# SL_Config_2E.net
KiCad netlist of a schematic drawn in Altium Designer
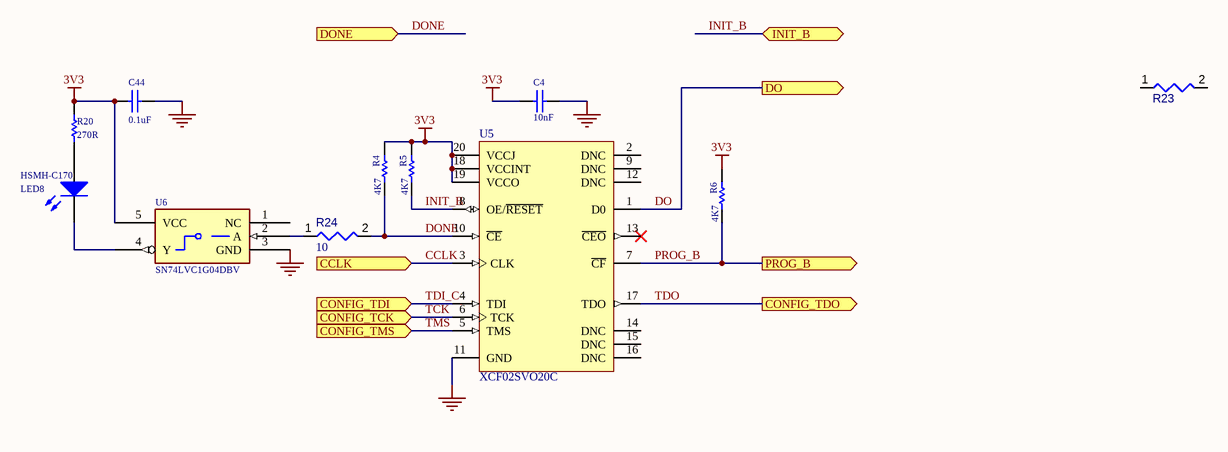
[diagram p0: SL_Config_2E.SchDoc]

(export (version "E")
  (design (tool "Eeschema 10.0.6"))
  (components
    (comp (ref "C4")
      (value "10nF")
      (footprint "CC1608-0603")
      (description "Capacitor")
      (libsource (lib "SpiritLevel_2E") (part "CAP"))
    )
    (comp (ref "C44")
      (value "0.1uF")
      (footprint "CC2012-0805")
      (description "Capacitor")
      (libsource (lib "SpiritLevel_2E") (part "CAP"))
    )
    (comp (ref "LED8")
      (value "HSMH-C170")
      (footprint "Spirit_Level_Project:SMD _LED")
      (description "Typical RED GaAs SMD LED Agilent make")
      (libsource (lib "SpiritLevel_2E") (part "HSMX-C670"))
    )
    (comp (ref "R4")
      (value "4K7")
      (footprint "Spirit_Level_Project:CR2012-0805")
      (description "Resistor")
      (libsource (lib "SpiritLevel_2E") (part "RES"))
    )
    (comp (ref "R5")
      (value "4K7")
      (footprint "Spirit_Level_Project:CR2012-0805")
      (description "Resistor")
      (libsource (lib "SpiritLevel_2E") (part "RES"))
    )
    (comp (ref "R6")
      (value "4K7")
      (footprint "Spirit_Level_Project:CR2012-0805")
      (description "Resistor")
      (libsource (lib "SpiritLevel_2E") (part "RES"))
    )
    (comp (ref "R20")
      (value "270R")
      (footprint "Spirit_Level_Project:CR2012-0805")
      (description "Resistor")
      (libsource (lib "SpiritLevel_2E") (part "RES"))
    )
    (comp (ref "R23")
      (value "Resistors")
      (description "Resistor")
      (libsource (lib "AES on LJ-AZ-064") (part "RES-2"))
    )
    (comp (ref "R24")
      (value "10")
      (footprint "RESC1005X40X25ML10T10")
      (description "Chip Resistor, 10 Ohm, +/- 5%, 0.063 W, -55 to 155 degC, 0402 (1005 Metric)")
      (fields (field (name "TOLERANCE") "5%") (field (name "POWER") "63mW"))
      (libsource (lib "AES on LJ-AZ-064") (part "RES-2"))
    )
    (comp (ref "U5")
      (value "XCF02SVO20C")
      (footprint "Spirit_Level_Project:VO20")
      (libsource (lib "SpiritLevel_2E") (part "XCF02SVO20C"))
    )
    (comp (ref "U6")
      (value "SN74LVC1G04DBV")
      (footprint "Spirit_Level_Project:SO-G5/P.95")
      (fields (field (name "MANUFACTURER") "TI"))
      (libsource (lib "SpiritLevel_2E") (part "SN74AHC1G04DBVR"))
    )
  )
  (nets
    (net (code "1") (name "/CCLK") (class "Default")
      (node (ref "U5") (pin "3") (pinfunction "CLK_3") (pintype "input"))
    )
    (net (code "2") (name "/DO") (class "Default")
      (node (ref "U5") (pin "1") (pinfunction "D0_1") (pintype "tri_state"))
    )
    (net (code "3") (name "/DONE") (class "Default")
      (node (ref "R24") (pin "2") (pinfunction "2_2") (pintype "passive"))
      (node (ref "R4") (pin "2") (pinfunction "2_2") (pintype "passive"))
      (node (ref "U5") (pin "10") (pinfunction "~{CE}_10") (pintype "input"))
    )
    (net (code "4") (name "/INIT_B") (class "Default")
      (node (ref "R5") (pin "2") (pinfunction "2_2") (pintype "passive"))
      (node (ref "U5") (pin "8") (pinfunction "OE/~{RESET}_8") (pintype "bidirectional"))
    )
    (net (code "5") (name "/PROG_B") (class "Default")
      (node (ref "R6") (pin "2") (pinfunction "2_2") (pintype "passive"))
      (node (ref "U5") (pin "7") (pinfunction "~{CF}_7") (pintype "open_collector"))
    )
    (net (code "6") (name "/TCK") (class "Default")
      (node (ref "U5") (pin "6") (pinfunction "TCK_6") (pintype "input"))
    )
    (net (code "7") (name "/TDI_C") (class "Default")
      (node (ref "U5") (pin "4") (pinfunction "TDI_4") (pintype "input"))
    )
    (net (code "8") (name "/TDO") (class "Default")
      (node (ref "U5") (pin "17") (pinfunction "TDO_17") (pintype "output"))
    )
    (net (code "9") (name "/TMS") (class "Default")
      (node (ref "U5") (pin "5") (pinfunction "TMS_5") (pintype "input"))
    )
    (net (code "10") (name "3V3") (class "Default")
      (node (ref "C4") (pin "1") (pinfunction "1_1") (pintype "passive"))
      (node (ref "C44") (pin "2") (pinfunction "2_2") (pintype "passive"))
      (node (ref "R20") (pin "2") (pinfunction "2_2") (pintype "passive"))
      (node (ref "R4") (pin "1") (pinfunction "1_1") (pintype "passive"))
      (node (ref "R5") (pin "1") (pinfunction "1_1") (pintype "passive"))
      (node (ref "R6") (pin "1") (pinfunction "1_1") (pintype "passive"))
      (node (ref "U5") (pin "18") (pinfunction "VCCINT_18") (pintype "power_in"))
      (node (ref "U5") (pin "19") (pinfunction "VCCO_19") (pintype "power_in"))
      (node (ref "U5") (pin "20") (pinfunction "VCCJ_20") (pintype "power_in"))
      (node (ref "U6") (pin "5") (pinfunction "VCC_5") (pintype "power_in"))
    )
    (net (code "11") (name "GND") (class "Default")
      (node (ref "C4") (pin "2") (pinfunction "2_2") (pintype "passive"))
      (node (ref "C44") (pin "1") (pinfunction "1_1") (pintype "passive"))
      (node (ref "U5") (pin "11") (pinfunction "GND_11") (pintype "power_in"))
      (node (ref "U6") (pin "3") (pinfunction "GND_3") (pintype "power_in"))
    )
    (net (code "12") (name "Net-(LED8-A)") (class "Default")
      (node (ref "LED8") (pin "1") (pinfunction "A_1") (pintype "passive"))
      (node (ref "R20") (pin "1") (pinfunction "1_1") (pintype "passive"))
    )
    (net (code "13") (name "Net-(LED8-K)") (class "Default")
      (node (ref "LED8") (pin "2") (pinfunction "K_2") (pintype "passive"))
      (node (ref "U6") (pin "4") (pinfunction "Y_4") (pintype "output"))
    )
    (net (code "14") (name "Net-(U6-A)") (class "Default")
      (node (ref "R24") (pin "1") (pinfunction "1_1") (pintype "passive"))
      (node (ref "U6") (pin "2") (pinfunction "A_2") (pintype "input"))
    )
    (net (code "15") (name "unconnected-(R23-Pad1)") (class "Default")
      (node (ref "R23") (pin "1") (pinfunction "1_1") (pintype "passive"))
    )
    (net (code "16") (name "unconnected-(R23-Pad2)") (class "Default")
      (node (ref "R23") (pin "2") (pinfunction "2_2") (pintype "passive"))
    )
    (net (code "17") (name "unconnected-(U5-DNC-Pad2)") (class "Default")
      (node (ref "U5") (pin "2") (pinfunction "DNC_2") (pintype "passive"))
    )
    (net (code "18") (name "unconnected-(U5-DNC-Pad9)") (class "Default")
      (node (ref "U5") (pin "9") (pinfunction "DNC_9") (pintype "passive"))
    )
    (net (code "19") (name "unconnected-(U5-DNC-Pad12)") (class "Default")
      (node (ref "U5") (pin "12") (pinfunction "DNC_12") (pintype "passive"))
    )
    (net (code "20") (name "unconnected-(U5-DNC-Pad14)") (class "Default")
      (node (ref "U5") (pin "14") (pinfunction "DNC_14") (pintype "passive"))
    )
    (net (code "21") (name "unconnected-(U5-DNC-Pad15)") (class "Default")
      (node (ref "U5") (pin "15") (pinfunction "DNC_15") (pintype "passive"))
    )
    (net (code "22") (name "unconnected-(U5-DNC-Pad16)") (class "Default")
      (node (ref "U5") (pin "16") (pinfunction "DNC_16") (pintype "passive"))
    )
    (net (code "23") (name "unconnected-(U5-~{CEO}-Pad13)") (class "Default")
      (node (ref "U5") (pin "13") (pinfunction "~{CEO}_13") (pintype "output+no_connect"))
    )
    (net (code "24") (name "unconnected-(U6-NC-Pad1)") (class "Default")
      (node (ref "U6") (pin "1") (pinfunction "NC_1") (pintype "passive"))
    )
  )
)
